# SimpleC64Cart.net
KiCad netlist of a schematic drawn in EAGLE
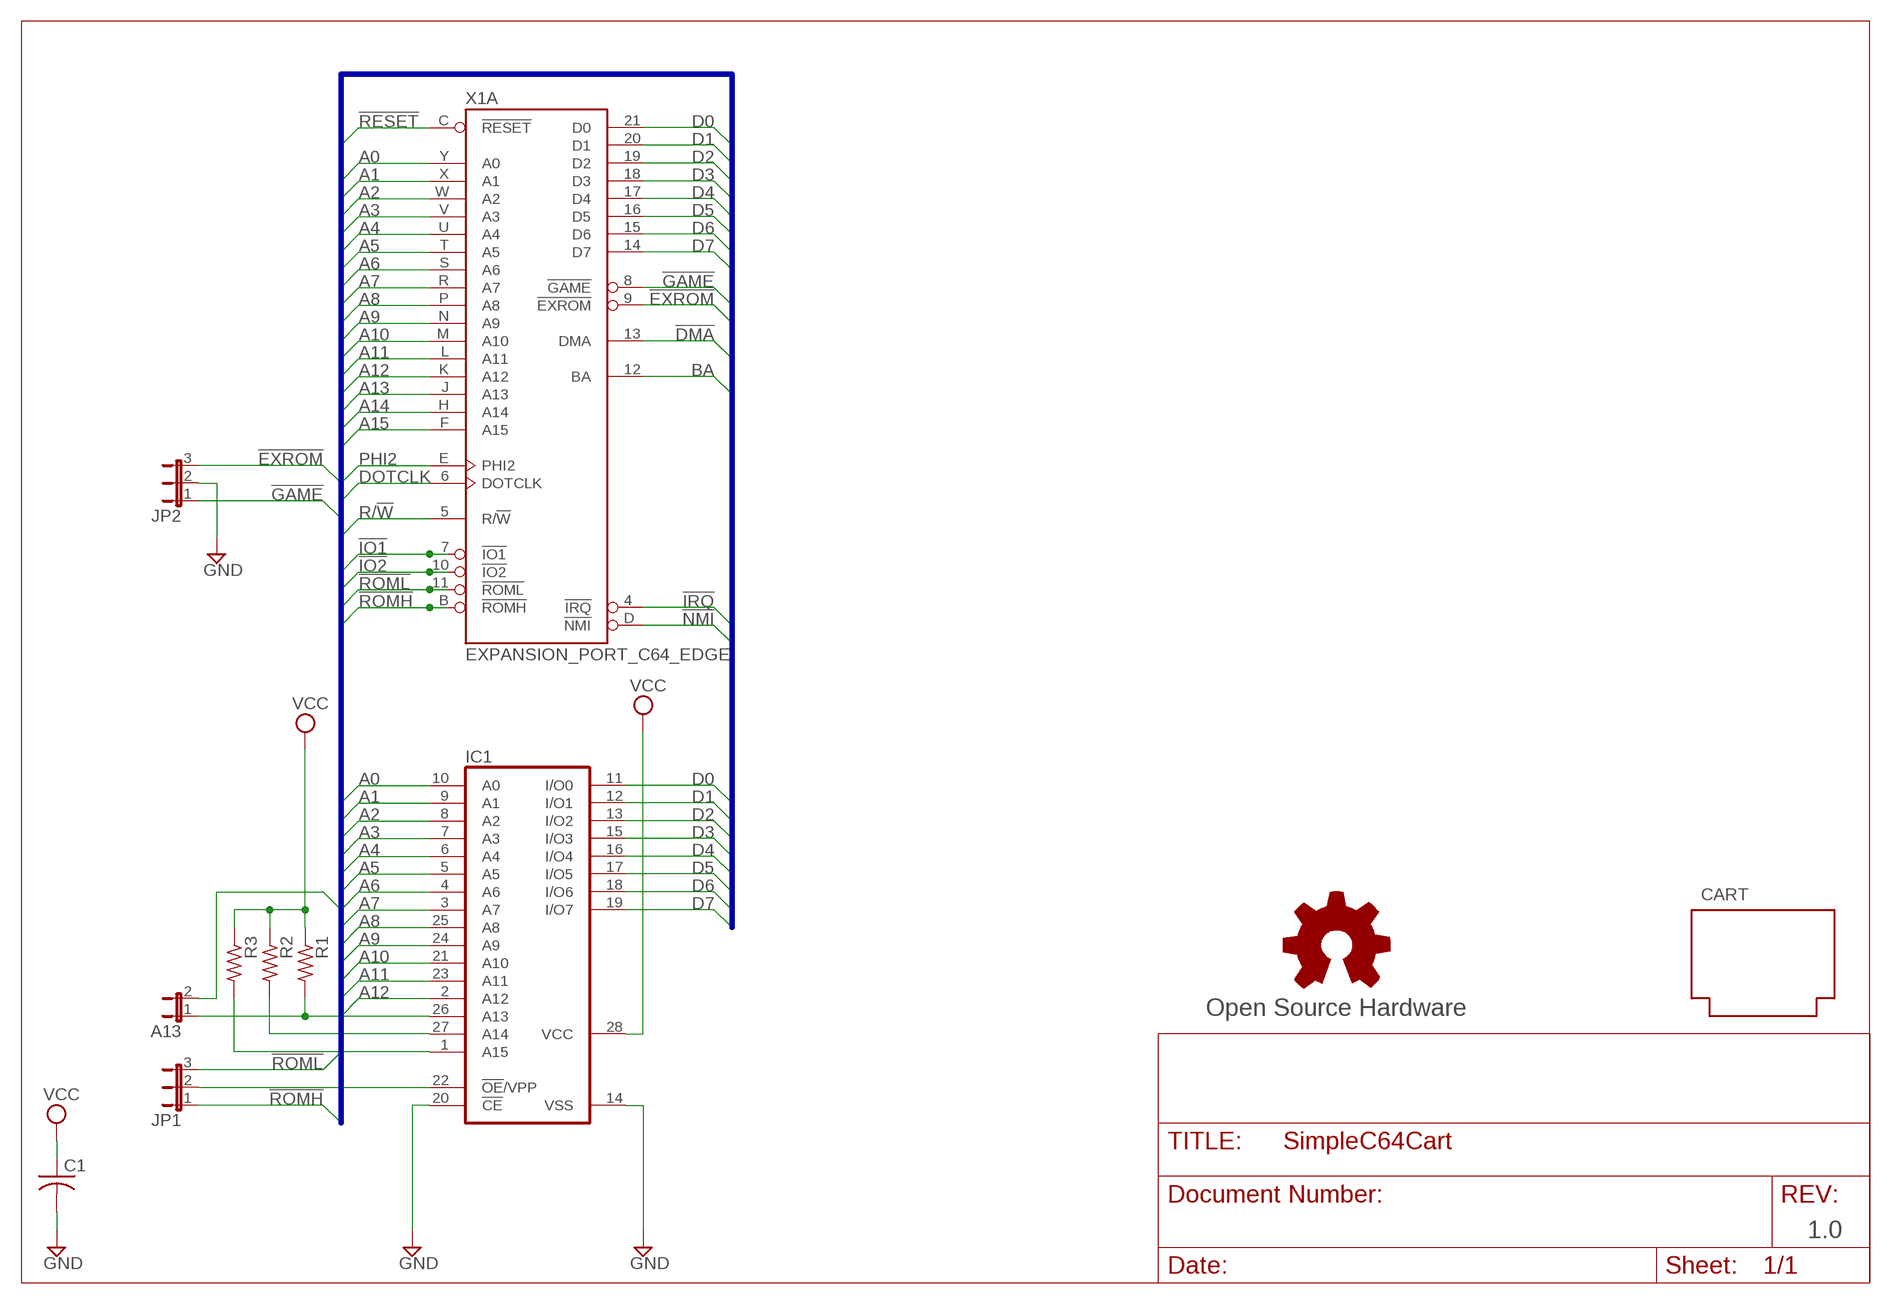
[diagram p0: schematic, sheet 1]

(export (version "E")
  (design (tool "Eeschema 10.0.6"))
  (components
    (comp (ref "A13")
      (value "JP1E")
      (footprint "eagle-import:JP1")
      (libsource (lib "eagle-import") (part "JP1E"))
    )
    (comp (ref "C1")
      (value "C-US025-025X050")
      (footprint "eagle-import:C025-025X050")
      (libsource (lib "eagle-import") (part "C-US025-025X050"))
    )
    (comp (ref "CART")
      (value "CARTRIDGE_C64")
      (footprint "eagle-import:CARTRIDGE_C64")
      (libsource (lib "eagle-import") (part "CARTRIDGE_C64"))
    )
    (comp (ref "GOLD_ORB_SM1")
      (value "Open Source Hardware")
      (footprint "eagle-import:OSHW_8MM")
      (libsource (lib "eagle-import") (part "OSHWLOGOLOGO8MM"))
    )
    (comp (ref "IC1")
      (value "27512G")
      (footprint "eagle-import:DIL28-6")
      (libsource (lib "eagle-import") (part "27512G"))
    )
    (comp (ref "JP1")
      (value "JP2E")
      (footprint "eagle-import:JP2")
      (libsource (lib "eagle-import") (part "JP2E"))
    )
    (comp (ref "JP2")
      (value "JP2E")
      (footprint "eagle-import:JP2")
      (libsource (lib "eagle-import") (part "JP2E"))
    )
    (comp (ref "R1")
      (value "R-US_0204/7")
      (footprint "eagle-import:0204_7")
      (libsource (lib "eagle-import") (part "R-US_0204/7"))
    )
    (comp (ref "R2")
      (value "R-US_0204/7")
      (footprint "eagle-import:0204_7")
      (libsource (lib "eagle-import") (part "R-US_0204/7"))
    )
    (comp (ref "R3")
      (value "R-US_0204/7")
      (footprint "eagle-import:0204_7")
      (libsource (lib "eagle-import") (part "R-US_0204/7"))
    )
    (comp (ref "X1")
      (value "EXPANSION_PORT_C64_EDGE")
      (footprint "eagle-import:MA100-22-2")
      (libsource (lib "eagle-import") (part "EXPANSION_PORT_C64_EDGE"))
    )
  )
  (nets
    (net (code "1") (name "/A0") (class "Default")
      (node (ref "IC1") (pin "10") (pinfunction "A0_10") (pintype "input"))
      (node (ref "X1") (pin "Y") (pinfunction "A0_Y") (pintype "bidirectional"))
    )
    (net (code "2") (name "/A1") (class "Default")
      (node (ref "IC1") (pin "9") (pinfunction "A1_9") (pintype "input"))
      (node (ref "X1") (pin "X") (pinfunction "A1_X") (pintype "bidirectional"))
    )
    (net (code "3") (name "/A2") (class "Default")
      (node (ref "IC1") (pin "8") (pinfunction "A2_8") (pintype "input"))
      (node (ref "X1") (pin "W") (pinfunction "A2_W") (pintype "bidirectional"))
    )
    (net (code "4") (name "/A3") (class "Default")
      (node (ref "IC1") (pin "7") (pinfunction "A3_7") (pintype "input"))
      (node (ref "X1") (pin "V") (pinfunction "A3_V") (pintype "bidirectional"))
    )
    (net (code "5") (name "/A4") (class "Default")
      (node (ref "IC1") (pin "6") (pinfunction "A4_6") (pintype "input"))
      (node (ref "X1") (pin "U") (pinfunction "A4_U") (pintype "bidirectional"))
    )
    (net (code "6") (name "/A5") (class "Default")
      (node (ref "IC1") (pin "5") (pinfunction "A5_5") (pintype "input"))
      (node (ref "X1") (pin "T") (pinfunction "A5_T") (pintype "bidirectional"))
    )
    (net (code "7") (name "/A6") (class "Default")
      (node (ref "IC1") (pin "4") (pinfunction "A6_4") (pintype "input"))
      (node (ref "X1") (pin "S") (pinfunction "A6_S") (pintype "bidirectional"))
    )
    (net (code "8") (name "/A7") (class "Default")
      (node (ref "IC1") (pin "3") (pinfunction "A7_3") (pintype "input"))
      (node (ref "X1") (pin "R") (pinfunction "A7_R") (pintype "bidirectional"))
    )
    (net (code "9") (name "/A8") (class "Default")
      (node (ref "IC1") (pin "25") (pinfunction "A8_25") (pintype "input"))
      (node (ref "X1") (pin "P") (pinfunction "A8_P") (pintype "bidirectional"))
    )
    (net (code "10") (name "/A9") (class "Default")
      (node (ref "IC1") (pin "24") (pinfunction "A9_24") (pintype "input"))
      (node (ref "X1") (pin "N") (pinfunction "A9_N") (pintype "bidirectional"))
    )
    (net (code "11") (name "/A10") (class "Default")
      (node (ref "IC1") (pin "21") (pinfunction "A10_21") (pintype "input"))
      (node (ref "X1") (pin "M") (pinfunction "A10_M") (pintype "bidirectional"))
    )
    (net (code "12") (name "/A11") (class "Default")
      (node (ref "IC1") (pin "23") (pinfunction "A11_23") (pintype "input"))
      (node (ref "X1") (pin "L") (pinfunction "A11_L") (pintype "bidirectional"))
    )
    (net (code "13") (name "/A12") (class "Default")
      (node (ref "IC1") (pin "2") (pinfunction "A12_2") (pintype "input"))
      (node (ref "X1") (pin "K") (pinfunction "A12_K") (pintype "bidirectional"))
    )
    (net (code "14") (name "/A13") (class "Default")
      (node (ref "A13") (pin "2") (pinfunction "2_2") (pintype "passive"))
      (node (ref "X1") (pin "J") (pinfunction "A13_J") (pintype "bidirectional"))
    )
    (net (code "15") (name "/A14") (class "Default")
      (node (ref "X1") (pin "H") (pinfunction "A14_H") (pintype "bidirectional"))
    )
    (net (code "16") (name "/A15") (class "Default")
      (node (ref "X1") (pin "F") (pinfunction "A15_F") (pintype "bidirectional"))
    )
    (net (code "17") (name "/BA") (class "Default")
      (node (ref "X1") (pin "12") (pinfunction "BA_12") (pintype "bidirectional"))
    )
    (net (code "18") (name "/D0") (class "Default")
      (node (ref "IC1") (pin "11") (pinfunction "I/O0_11") (pintype "tri_state"))
      (node (ref "X1") (pin "21") (pinfunction "D0_21") (pintype "bidirectional"))
    )
    (net (code "19") (name "/D1") (class "Default")
      (node (ref "IC1") (pin "12") (pinfunction "I/O1_12") (pintype "tri_state"))
      (node (ref "X1") (pin "20") (pinfunction "D1_20") (pintype "bidirectional"))
    )
    (net (code "20") (name "/D2") (class "Default")
      (node (ref "IC1") (pin "13") (pinfunction "I/O2_13") (pintype "tri_state"))
      (node (ref "X1") (pin "19") (pinfunction "D2_19") (pintype "bidirectional"))
    )
    (net (code "21") (name "/D3") (class "Default")
      (node (ref "IC1") (pin "15") (pinfunction "I/O3_15") (pintype "tri_state"))
      (node (ref "X1") (pin "18") (pinfunction "D3_18") (pintype "bidirectional"))
    )
    (net (code "22") (name "/D4") (class "Default")
      (node (ref "IC1") (pin "16") (pinfunction "I/O4_16") (pintype "tri_state"))
      (node (ref "X1") (pin "17") (pinfunction "D4_17") (pintype "bidirectional"))
    )
    (net (code "23") (name "/D5") (class "Default")
      (node (ref "IC1") (pin "17") (pinfunction "I/O5_17") (pintype "tri_state"))
      (node (ref "X1") (pin "16") (pinfunction "D5_16") (pintype "bidirectional"))
    )
    (net (code "24") (name "/D6") (class "Default")
      (node (ref "IC1") (pin "18") (pinfunction "I/O6_18") (pintype "tri_state"))
      (node (ref "X1") (pin "15") (pinfunction "D6_15") (pintype "bidirectional"))
    )
    (net (code "25") (name "/D7") (class "Default")
      (node (ref "IC1") (pin "19") (pinfunction "I/O7_19") (pintype "tri_state"))
      (node (ref "X1") (pin "14") (pinfunction "D7_14") (pintype "bidirectional"))
    )
    (net (code "26") (name "/DOTCLK") (class "Default")
      (node (ref "X1") (pin "6") (pinfunction "DOTCLK_6") (pintype "output"))
    )
    (net (code "27") (name "/PHI2") (class "Default")
      (node (ref "X1") (pin "E") (pinfunction "PHI2_E") (pintype "output"))
    )
    (net (code "28") (name "/R{slash}~{W}") (class "Default")
      (node (ref "X1") (pin "5") (pinfunction "R/~{W}_5") (pintype "bidirectional"))
    )
    (net (code "29") (name "/~{DMA}") (class "Default")
      (node (ref "X1") (pin "13") (pinfunction "DMA_13") (pintype "bidirectional"))
    )
    (net (code "30") (name "/~{EXROM}") (class "Default")
      (node (ref "JP2") (pin "3") (pinfunction "3_3") (pintype "passive"))
      (node (ref "X1") (pin "9") (pinfunction "~{EXROM}_9") (pintype "input"))
    )
    (net (code "31") (name "/~{GAME}") (class "Default")
      (node (ref "JP2") (pin "1") (pinfunction "1_1") (pintype "passive"))
      (node (ref "X1") (pin "8") (pinfunction "~{GAME}_8") (pintype "input"))
    )
    (net (code "32") (name "/~{IO1}") (class "Default")
      (node (ref "X1") (pin "7") (pinfunction "~{IO1}_7") (pintype "output"))
    )
    (net (code "33") (name "/~{IO2}") (class "Default")
      (node (ref "X1") (pin "10") (pinfunction "~{IO2}_10") (pintype "output"))
    )
    (net (code "34") (name "/~{IRQ}") (class "Default")
      (node (ref "X1") (pin "4") (pinfunction "~{IRQ}_4") (pintype "open_collector"))
    )
    (net (code "35") (name "/~{NMI}") (class "Default")
      (node (ref "X1") (pin "D") (pinfunction "~{NMI}_D") (pintype "open_collector"))
    )
    (net (code "36") (name "/~{RESET}") (class "Default")
      (node (ref "X1") (pin "C") (pinfunction "~{RESET}_C") (pintype "open_collector"))
    )
    (net (code "37") (name "/~{ROMH}") (class "Default")
      (node (ref "JP1") (pin "1") (pinfunction "1_1") (pintype "passive"))
      (node (ref "X1") (pin "B") (pinfunction "~{ROMH}_B") (pintype "output"))
    )
    (net (code "38") (name "/~{ROML}") (class "Default")
      (node (ref "JP1") (pin "3") (pinfunction "3_3") (pintype "passive"))
      (node (ref "X1") (pin "11") (pinfunction "~{ROML}_11") (pintype "output"))
    )
    (net (code "39") (name "GND") (class "Default")
      (node (ref "C1") (pin "2") (pinfunction "2_2") (pintype "passive"))
      (node (ref "IC1") (pin "14") (pinfunction "VSS_14") (pintype "power_in"))
      (node (ref "IC1") (pin "20") (pinfunction "~{CE}_20") (pintype "input"))
      (node (ref "JP2") (pin "2") (pinfunction "2_2") (pintype "passive"))
    )
    (net (code "40") (name "Net-(IC1-A13)") (class "Default")
      (node (ref "A13") (pin "1") (pinfunction "1_1") (pintype "passive"))
      (node (ref "IC1") (pin "26") (pinfunction "A13_26") (pintype "input"))
      (node (ref "R1") (pin "2") (pinfunction "2_2") (pintype "passive"))
    )
    (net (code "41") (name "Net-(IC1-A14)") (class "Default")
      (node (ref "IC1") (pin "27") (pinfunction "A14_27") (pintype "input"))
      (node (ref "R2") (pin "2") (pinfunction "2_2") (pintype "passive"))
    )
    (net (code "42") (name "Net-(IC1-A15)") (class "Default")
      (node (ref "IC1") (pin "1") (pinfunction "A15_1") (pintype "input"))
      (node (ref "R3") (pin "2") (pinfunction "2_2") (pintype "passive"))
    )
    (net (code "43") (name "Net-(IC1-~{OE}{slash}VPP)") (class "Default")
      (node (ref "IC1") (pin "22") (pinfunction "~{OE}/VPP_22") (pintype "input"))
      (node (ref "JP1") (pin "2") (pinfunction "2_2") (pintype "passive"))
    )
    (net (code "44") (name "VCC") (class "Default")
      (node (ref "C1") (pin "1") (pinfunction "1_1") (pintype "passive"))
      (node (ref "IC1") (pin "28") (pinfunction "VCC_28") (pintype "power_in"))
      (node (ref "R1") (pin "1") (pinfunction "1_1") (pintype "passive"))
      (node (ref "R2") (pin "1") (pinfunction "1_1") (pintype "passive"))
      (node (ref "R3") (pin "1") (pinfunction "1_1") (pintype "passive"))
    )
  )
)
